# MRCS-PCR-SIN03-Breakout.net
KiCad netlist of a schematic drawn in EAGLE
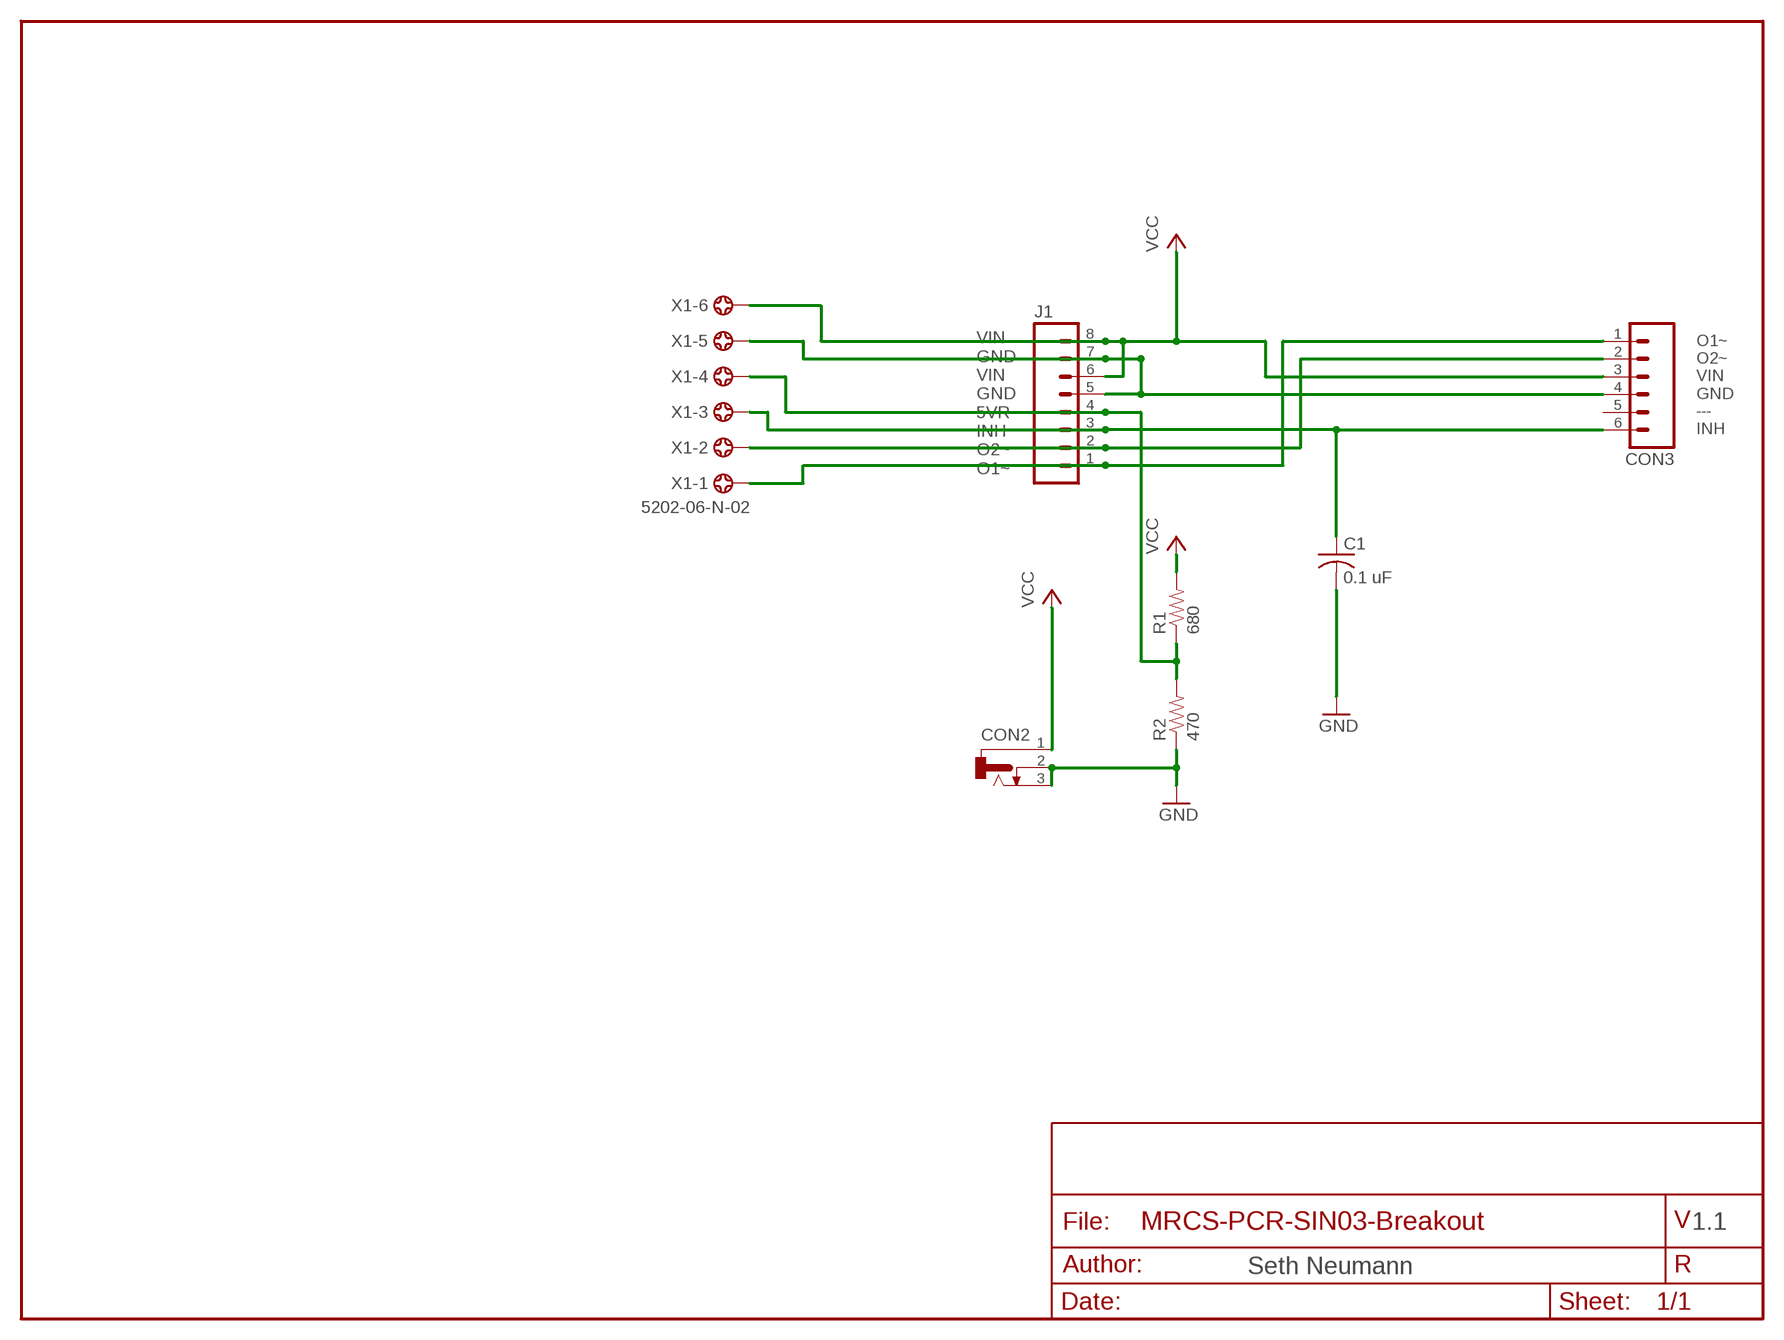
[diagram p0: schematic, sheet 1]

(export (version "E")
  (design (tool "Eeschema 10.0.6"))
  (components
    (comp (ref "C1")
      (value "0.1 uF")
      (footprint "eagle-import:C-PTH-0.100")
      (libsource (lib "eagle-import") (part "CAPPTH2"))
    )
    (comp (ref "CON2")
      (value "CONNECTOR-DC-POWER-RA")
      (footprint "eagle-import:DCJ0202")
      (libsource (lib "eagle-import") (part "CONNECTOR-DC-POWER-RA"))
    )
    (comp (ref "CON3")
      (value "CONNECTOR-M06POLAR")
      (footprint "eagle-import:MOLEX-1X6")
      (libsource (lib "eagle-import") (part "CONNECTOR-M06POLAR"))
    )
    (comp (ref "J1")
      (value "CONNECTOR-M08LOCK")
      (footprint "eagle-import:1X08_LOCK")
      (libsource (lib "eagle-import") (part "CONNECTOR-M08LOCK"))
    )
    (comp (ref "R1")
      (value "680")
      (footprint "eagle-import:AXIAL-0.4-RES")
      (libsource (lib "eagle-import") (part "RPTH04"))
    )
    (comp (ref "R2")
      (value "470")
      (footprint "eagle-import:AXIAL-0.4-RES")
      (libsource (lib "eagle-import") (part "RPTH04"))
    )
    (comp (ref "X1")
      (value "5202-06-N-02")
      (footprint "eagle-import:5202-06-N-02")
      (libsource (lib "eagle-import") (part "5202-06-N-02"))
    )
  )
  (nets
    (net (code "1") (name "GND") (class "Default")
      (node (ref "C1") (pin "2") (pinfunction "2_2") (pintype "passive"))
      (node (ref "CON2") (pin "2") (pinfunction "2_2") (pintype "passive"))
      (node (ref "CON2") (pin "3") (pinfunction "3_3") (pintype "passive"))
      (node (ref "CON3") (pin "4") (pinfunction "4_4") (pintype "passive"))
      (node (ref "J1") (pin "5") (pinfunction "5_5") (pintype "passive"))
      (node (ref "J1") (pin "7") (pinfunction "7_7") (pintype "passive"))
      (node (ref "R2") (pin "P$1") (pinfunction "1_P$1") (pintype "passive"))
      (node (ref "X1") (pin "5") (pinfunction "1_5") (pintype "passive"))
    )
    (net (code "2") (name "Net-(CON3-Pad1)") (class "Default")
      (node (ref "CON3") (pin "1") (pinfunction "1_1") (pintype "passive"))
      (node (ref "J1") (pin "1") (pinfunction "1_1") (pintype "passive"))
      (node (ref "X1") (pin "1") (pinfunction "1_1") (pintype "passive"))
    )
    (net (code "3") (name "Net-(R1-1)") (class "Default")
      (node (ref "J1") (pin "4") (pinfunction "4_4") (pintype "passive"))
      (node (ref "R1") (pin "P$1") (pinfunction "1_P$1") (pintype "passive"))
      (node (ref "R2") (pin "P$2") (pinfunction "2_P$2") (pintype "passive"))
      (node (ref "X1") (pin "4") (pinfunction "1_4") (pintype "passive"))
    )
    (net (code "4") (name "Net-(X1B-1)") (class "Default")
      (node (ref "CON3") (pin "2") (pinfunction "2_2") (pintype "passive"))
      (node (ref "J1") (pin "2") (pinfunction "2_2") (pintype "passive"))
      (node (ref "X1") (pin "2") (pinfunction "1_2") (pintype "passive"))
    )
    (net (code "5") (name "Net-(X1C-1)") (class "Default")
      (node (ref "C1") (pin "1") (pinfunction "1_1") (pintype "passive"))
      (node (ref "CON3") (pin "6") (pinfunction "6_6") (pintype "passive"))
      (node (ref "J1") (pin "3") (pinfunction "3_3") (pintype "passive"))
      (node (ref "X1") (pin "3") (pinfunction "1_3") (pintype "passive"))
    )
    (net (code "6") (name "VCC") (class "Default")
      (node (ref "CON2") (pin "1") (pinfunction "1_1") (pintype "passive"))
      (node (ref "CON3") (pin "3") (pinfunction "3_3") (pintype "passive"))
      (node (ref "J1") (pin "6") (pinfunction "6_6") (pintype "passive"))
      (node (ref "J1") (pin "8") (pinfunction "8_8") (pintype "passive"))
      (node (ref "R1") (pin "P$2") (pinfunction "2_P$2") (pintype "passive"))
      (node (ref "X1") (pin "6") (pinfunction "1_6") (pintype "passive"))
    )
    (net (code "7") (name "unconnected-(CON3-Pad5)") (class "Default")
      (node (ref "CON3") (pin "5") (pinfunction "5_5") (pintype "passive"))
    )
  )
)
